# Synth.net
KiCad netlist of a schematic drawn in Altium Designer
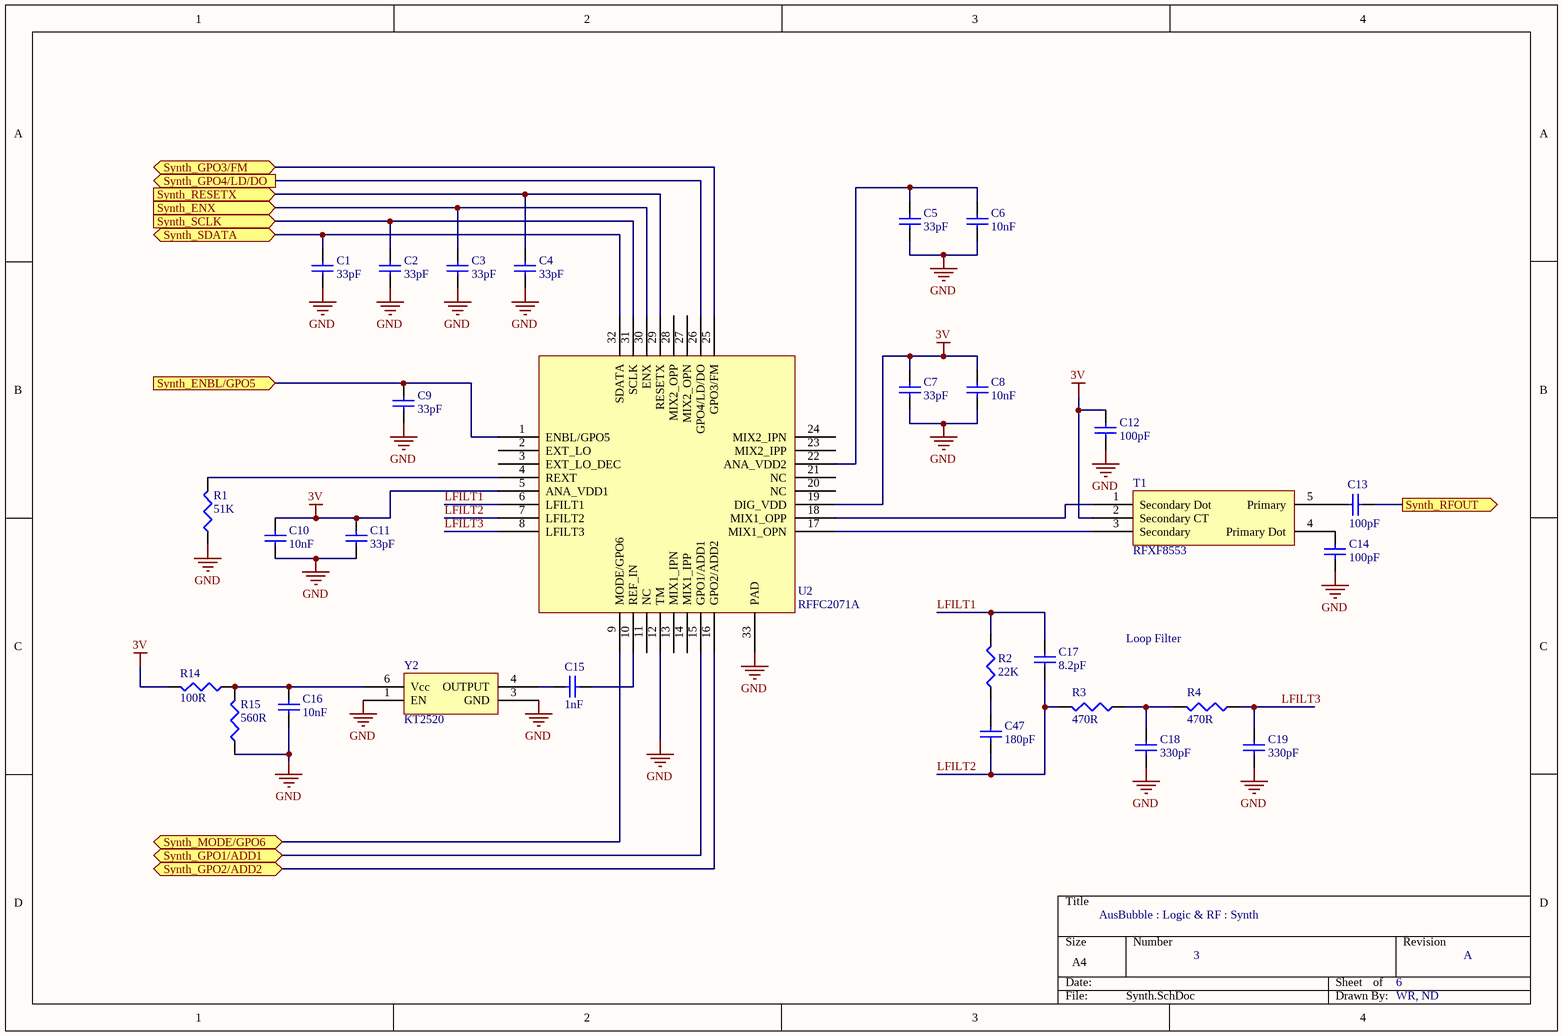
[diagram p0: Synth.SchDoc]

(export (version "E")
  (design (tool "Eeschema 10.0.6"))
  (components
    (comp (ref "C1")
      (value "33pF")
      (footprint "1608[0603]")
      (description "Capacitor (Semiconductor SIM Model)")
      (fields (field (name "Comment") "Cap Semi") (field (name "PUBLISHER") "Altium Limited"))
      (libsource (lib "Miscellaneous Devices") (part "Cap Semi"))
    )
    (comp (ref "C2")
      (value "33pF")
      (footprint "1608[0603]")
      (description "Capacitor (Semiconductor SIM Model)")
      (fields (field (name "Comment") "Cap Semi") (field (name "PUBLISHER") "Altium Limited"))
      (libsource (lib "Miscellaneous Devices") (part "Cap Semi"))
    )
    (comp (ref "C3")
      (value "33pF")
      (footprint "1608[0603]")
      (description "Capacitor (Semiconductor SIM Model)")
      (fields (field (name "Comment") "Cap Semi") (field (name "PUBLISHER") "Altium Limited"))
      (libsource (lib "Miscellaneous Devices") (part "Cap Semi"))
    )
    (comp (ref "C4")
      (value "33pF")
      (footprint "1608[0603]")
      (description "Capacitor (Semiconductor SIM Model)")
      (fields (field (name "Comment") "Cap Semi") (field (name "PUBLISHER") "Altium Limited"))
      (libsource (lib "Miscellaneous Devices") (part "Cap Semi"))
    )
    (comp (ref "C5")
      (value "33pF")
      (footprint "1608[0603]")
      (description "Capacitor (Semiconductor SIM Model)")
      (fields (field (name "Comment") "Cap Semi") (field (name "PUBLISHER") "Altium Limited"))
      (libsource (lib "Miscellaneous Devices") (part "Cap Semi"))
    )
    (comp (ref "C6")
      (value "10nF")
      (footprint "1608[0603]")
      (description "Capacitor (Semiconductor SIM Model)")
      (fields (field (name "Comment") "Cap Semi") (field (name "PUBLISHER") "Altium Limited"))
      (libsource (lib "Miscellaneous Devices") (part "Cap Semi"))
    )
    (comp (ref "C7")
      (value "33pF")
      (footprint "1608[0603]")
      (description "Capacitor (Semiconductor SIM Model)")
      (fields (field (name "Comment") "Cap Semi") (field (name "PUBLISHER") "Altium Limited"))
      (libsource (lib "Miscellaneous Devices") (part "Cap Semi"))
    )
    (comp (ref "C8")
      (value "10nF")
      (footprint "1608[0603]")
      (description "Capacitor (Semiconductor SIM Model)")
      (fields (field (name "Comment") "Cap Semi") (field (name "PUBLISHER") "Altium Limited"))
      (libsource (lib "Miscellaneous Devices") (part "Cap Semi"))
    )
    (comp (ref "C9")
      (value "33pF")
      (footprint "1608[0603]")
      (description "Capacitor (Semiconductor SIM Model)")
      (fields (field (name "Comment") "Cap Semi") (field (name "PUBLISHER") "Altium Limited"))
      (libsource (lib "Miscellaneous Devices") (part "Cap Semi"))
    )
    (comp (ref "C10")
      (value "10nF")
      (footprint "1608[0603]")
      (description "Capacitor (Semiconductor SIM Model)")
      (fields (field (name "Comment") "Cap Semi") (field (name "PUBLISHER") "Altium Limited"))
      (libsource (lib "Miscellaneous Devices") (part "Cap Semi"))
    )
    (comp (ref "C11")
      (value "33pF")
      (footprint "1608[0603]")
      (description "Capacitor (Semiconductor SIM Model)")
      (fields (field (name "Comment") "Cap Semi") (field (name "PUBLISHER") "Altium Limited"))
      (libsource (lib "Miscellaneous Devices") (part "Cap Semi"))
    )
    (comp (ref "C12")
      (value "100pF")
      (footprint "1608[0603]")
      (description "Capacitor (Semiconductor SIM Model)")
      (fields (field (name "Comment") "Cap Semi") (field (name "PUBLISHER") "Altium Limited"))
      (libsource (lib "Miscellaneous Devices") (part "Cap Semi"))
    )
    (comp (ref "C13")
      (value "100pF")
      (footprint "1608[0603]")
      (description "Capacitor (Semiconductor SIM Model)")
      (fields (field (name "Comment") "Cap Semi") (field (name "PUBLISHER") "Altium Limited"))
      (libsource (lib "Miscellaneous Devices") (part "Cap Semi"))
    )
    (comp (ref "C14")
      (value "100pF")
      (footprint "1608[0603]")
      (description "Capacitor (Semiconductor SIM Model)")
      (fields (field (name "Comment") "Cap Semi") (field (name "PUBLISHER") "Altium Limited"))
      (libsource (lib "Miscellaneous Devices") (part "Cap Semi"))
    )
    (comp (ref "C15")
      (value "1nF")
      (footprint "1608[0603]")
      (description "Capacitor (Semiconductor SIM Model)")
      (fields (field (name "Comment") "Cap Semi") (field (name "PUBLISHER") "Altium Limited"))
      (libsource (lib "Miscellaneous Devices") (part "Cap Semi"))
    )
    (comp (ref "C16")
      (value "10nF")
      (footprint "1608[0603]")
      (description "Capacitor (Semiconductor SIM Model)")
      (fields (field (name "Comment") "Cap Semi") (field (name "PUBLISHER") "Altium Limited"))
      (libsource (lib "Miscellaneous Devices") (part "Cap Semi"))
    )
    (comp (ref "C17")
      (value "8.2pF")
      (footprint "1608[0603]")
      (description "Capacitor (Semiconductor SIM Model)")
      (fields (field (name "Comment") "Cap Semi") (field (name "PUBLISHER") "Altium Limited"))
      (libsource (lib "Miscellaneous Devices") (part "Cap Semi"))
    )
    (comp (ref "C18")
      (value "330pF")
      (footprint "1608[0603]")
      (description "Capacitor (Semiconductor SIM Model)")
      (fields (field (name "Comment") "Cap Semi") (field (name "PUBLISHER") "Altium Limited"))
      (libsource (lib "Miscellaneous Devices") (part "Cap Semi"))
    )
    (comp (ref "C19")
      (value "330pF")
      (footprint "1608[0603]")
      (description "Capacitor (Semiconductor SIM Model)")
      (fields (field (name "Comment") "Cap Semi") (field (name "PUBLISHER") "Altium Limited"))
      (libsource (lib "Miscellaneous Devices") (part "Cap Semi"))
    )
    (comp (ref "C47")
      (value "180pF")
      (footprint "1608[0603]")
      (description "Capacitor (Semiconductor SIM Model)")
      (fields (field (name "Comment") "Cap Semi") (field (name "PUBLISHER") "Altium Limited"))
      (libsource (lib "Miscellaneous Devices") (part "Cap Semi"))
    )
    (comp (ref "R1")
      (value "51K")
      (footprint "J1-0603")
      (description "Resistor")
      (fields (field (name "Comment") "Res3") (field (name "PUBLISHER") "Altium Limited"))
      (libsource (lib "Miscellaneous Devices") (part "Res3"))
    )
    (comp (ref "R2")
      (value "22K")
      (footprint "J1-0603")
      (description "Resistor")
      (fields (field (name "Comment") "Res3") (field (name "PUBLISHER") "Altium Limited"))
      (libsource (lib "Miscellaneous Devices") (part "Res3"))
    )
    (comp (ref "R3")
      (value "470R")
      (footprint "J1-0603")
      (description "Resistor")
      (fields (field (name "Comment") "Res3") (field (name "PUBLISHER") "Altium Limited"))
      (libsource (lib "Miscellaneous Devices") (part "Res3"))
    )
    (comp (ref "R4")
      (value "470R")
      (footprint "J1-0603")
      (description "Resistor")
      (fields (field (name "Comment") "Res3") (field (name "PUBLISHER") "Altium Limited"))
      (libsource (lib "Miscellaneous Devices") (part "Res3"))
    )
    (comp (ref "R14")
      (value "100R")
      (footprint "J1-0603")
      (description "Resistor")
      (fields (field (name "Comment") "Res3") (field (name "PUBLISHER") "Altium Limited"))
      (libsource (lib "Miscellaneous Devices") (part "Res3"))
    )
    (comp (ref "R15")
      (value "560R")
      (footprint "J1-0603")
      (description "Resistor")
      (fields (field (name "Comment") "Res3") (field (name "PUBLISHER") "Altium Limited"))
      (libsource (lib "Miscellaneous Devices") (part "Res3"))
    )
    (comp (ref "T1")
      (value "RFXF8553")
      (footprint "RFXF8553")
      (description "1:4 SMT TRANSFORMER")
      (libsource (lib "Logic_RF_Component_Symbols") (part "RFXF8553"))
    )
    (comp (ref "U2")
      (value "RFFC2071A")
      (footprint "QFN50P500X500-32WAL")
      (description "2.7GHz RF SYNTHESIZER/VCO WITH INTEGRATED RF MIXER")
      (libsource (lib "Logic_RF_Component_Symbols") (part "RFFC2071"))
    )
    (comp (ref "Y2")
      (value "KT2520")
      (footprint "KT2520")
      (description "Temperature-Compensated Crystal Oscillator (TCXO) KT2520")
      (libsource (lib "Logic_RF_Component_Symbols") (part "KT2520"))
    )
  )
  (nets
    (net (code "1") (name "/LFILT1") (class "Default")
      (node (ref "C17") (pin "2") (pinfunction "2_2") (pintype "passive"))
      (node (ref "R2") (pin "2") (pinfunction "2_2") (pintype "passive"))
      (node (ref "U2") (pin "6") (pinfunction "LFILT1_6") (pintype "passive"))
    )
    (net (code "2") (name "/LFILT2") (class "Default")
      (node (ref "C17") (pin "1") (pinfunction "1_1") (pintype "passive"))
      (node (ref "C47") (pin "1") (pinfunction "1_1") (pintype "passive"))
      (node (ref "R3") (pin "2") (pinfunction "2_2") (pintype "passive"))
      (node (ref "U2") (pin "7") (pinfunction "LFILT2_7") (pintype "passive"))
    )
    (net (code "3") (name "/LFILT3") (class "Default")
      (node (ref "C19") (pin "2") (pinfunction "2_2") (pintype "passive"))
      (node (ref "R4") (pin "1") (pinfunction "1_1") (pintype "passive"))
      (node (ref "U2") (pin "8") (pinfunction "LFILT3_8") (pintype "passive"))
    )
    (net (code "4") (name "/Synth_ENBL{slash}GPO5") (class "Default")
      (node (ref "C9") (pin "2") (pinfunction "2_2") (pintype "passive"))
      (node (ref "U2") (pin "1") (pinfunction "ENBL/GPO5_1") (pintype "passive"))
    )
    (net (code "5") (name "/Synth_ENX") (class "Default")
      (node (ref "C3") (pin "2") (pinfunction "2_2") (pintype "passive"))
      (node (ref "U2") (pin "30") (pinfunction "ENX_30") (pintype "passive"))
    )
    (net (code "6") (name "/Synth_GPO1{slash}ADD1") (class "Default")
      (node (ref "U2") (pin "15") (pinfunction "GPO1/ADD1_15") (pintype "passive"))
    )
    (net (code "7") (name "/Synth_GPO2{slash}ADD2") (class "Default")
      (node (ref "U2") (pin "16") (pinfunction "GPO2/ADD2_16") (pintype "passive"))
    )
    (net (code "8") (name "/Synth_GPO3{slash}FM") (class "Default")
      (node (ref "U2") (pin "25") (pinfunction "GPO3/FM_25") (pintype "passive"))
    )
    (net (code "9") (name "/Synth_GPO4{slash}LD{slash}DO") (class "Default")
      (node (ref "U2") (pin "26") (pinfunction "GPO4/LD/DO_26") (pintype "passive"))
    )
    (net (code "10") (name "/Synth_MODE{slash}GPO6") (class "Default")
      (node (ref "U2") (pin "9") (pinfunction "MODE/GPO6_9") (pintype "passive"))
    )
    (net (code "11") (name "/Synth_RESETX") (class "Default")
      (node (ref "C4") (pin "2") (pinfunction "2_2") (pintype "passive"))
      (node (ref "U2") (pin "29") (pinfunction "RESETX_29") (pintype "passive"))
    )
    (net (code "12") (name "/Synth_RFOUT") (class "Default")
      (node (ref "C13") (pin "2") (pinfunction "2_2") (pintype "passive"))
    )
    (net (code "13") (name "/Synth_SCLK") (class "Default")
      (node (ref "C2") (pin "2") (pinfunction "2_2") (pintype "passive"))
      (node (ref "U2") (pin "31") (pinfunction "SCLK_31") (pintype "passive"))
    )
    (net (code "14") (name "/Synth_SDATA") (class "Default")
      (node (ref "C1") (pin "2") (pinfunction "2_2") (pintype "passive"))
      (node (ref "U2") (pin "32") (pinfunction "SDATA_32") (pintype "passive"))
    )
    (net (code "15") (name "3V") (class "Default")
      (node (ref "C10") (pin "2") (pinfunction "2_2") (pintype "passive"))
      (node (ref "C11") (pin "2") (pinfunction "2_2") (pintype "passive"))
      (node (ref "C12") (pin "1") (pinfunction "1_1") (pintype "passive"))
      (node (ref "C7") (pin "1") (pinfunction "1_1") (pintype "passive"))
      (node (ref "C8") (pin "1") (pinfunction "1_1") (pintype "passive"))
      (node (ref "R14") (pin "2") (pinfunction "2_2") (pintype "passive"))
      (node (ref "T1") (pin "2") (pinfunction "Secondary_CT_2") (pintype "passive"))
      (node (ref "U2") (pin "19") (pinfunction "DIG_VDD_19") (pintype "passive"))
      (node (ref "U2") (pin "5") (pinfunction "ANA_VDD1_5") (pintype "passive"))
    )
    (net (code "16") (name "GND") (class "Default")
      (node (ref "C1") (pin "1") (pinfunction "1_1") (pintype "passive"))
      (node (ref "C10") (pin "1") (pinfunction "1_1") (pintype "passive"))
      (node (ref "C11") (pin "1") (pinfunction "1_1") (pintype "passive"))
      (node (ref "C12") (pin "2") (pinfunction "2_2") (pintype "passive"))
      (node (ref "C14") (pin "1") (pinfunction "1_1") (pintype "passive"))
      (node (ref "C16") (pin "1") (pinfunction "1_1") (pintype "passive"))
      (node (ref "C18") (pin "1") (pinfunction "1_1") (pintype "passive"))
      (node (ref "C19") (pin "1") (pinfunction "1_1") (pintype "passive"))
      (node (ref "C2") (pin "1") (pinfunction "1_1") (pintype "passive"))
      (node (ref "C3") (pin "1") (pinfunction "1_1") (pintype "passive"))
      (node (ref "C4") (pin "1") (pinfunction "1_1") (pintype "passive"))
      (node (ref "C5") (pin "2") (pinfunction "2_2") (pintype "passive"))
      (node (ref "C6") (pin "2") (pinfunction "2_2") (pintype "passive"))
      (node (ref "C7") (pin "2") (pinfunction "2_2") (pintype "passive"))
      (node (ref "C8") (pin "2") (pinfunction "2_2") (pintype "passive"))
      (node (ref "C9") (pin "1") (pinfunction "1_1") (pintype "passive"))
      (node (ref "R1") (pin "1") (pinfunction "1_1") (pintype "passive"))
      (node (ref "R15") (pin "1") (pinfunction "1_1") (pintype "passive"))
      (node (ref "U2") (pin "12") (pinfunction "TM_12") (pintype "passive"))
      (node (ref "U2") (pin "33") (pinfunction "PAD_33") (pintype "passive"))
      (node (ref "Y2") (pin "1") (pinfunction "EN_1") (pintype "passive"))
      (node (ref "Y2") (pin "3") (pinfunction "GND_3") (pintype "passive"))
    )
    (net (code "17") (name "Net-(C18-Pad2)") (class "Default")
      (node (ref "C18") (pin "2") (pinfunction "2_2") (pintype "passive"))
      (node (ref "R3") (pin "1") (pinfunction "1_1") (pintype "passive"))
      (node (ref "R4") (pin "2") (pinfunction "2_2") (pintype "passive"))
    )
    (net (code "18") (name "Net-(C47-Pad2)") (class "Default")
      (node (ref "C47") (pin "2") (pinfunction "2_2") (pintype "passive"))
      (node (ref "R2") (pin "1") (pinfunction "1_1") (pintype "passive"))
    )
    (net (code "19") (name "Net-(T1-Primary)") (class "Default")
      (node (ref "C13") (pin "1") (pinfunction "1_1") (pintype "passive"))
      (node (ref "T1") (pin "5") (pinfunction "Primary_5") (pintype "passive"))
    )
    (net (code "20") (name "Net-(T1-Primary_Dot)") (class "Default")
      (node (ref "C14") (pin "2") (pinfunction "2_2") (pintype "passive"))
      (node (ref "T1") (pin "4") (pinfunction "Primary_Dot_4") (pintype "passive"))
    )
    (net (code "21") (name "Net-(T1-Secondary)") (class "Default")
      (node (ref "T1") (pin "3") (pinfunction "Secondary_3") (pintype "passive"))
      (node (ref "U2") (pin "17") (pinfunction "MIX1_OPN_17") (pintype "passive"))
    )
    (net (code "22") (name "Net-(T1-Secondary_Dot)") (class "Default")
      (node (ref "T1") (pin "1") (pinfunction "Secondary_Dot_1") (pintype "passive"))
      (node (ref "U2") (pin "18") (pinfunction "MIX1_OPP_18") (pintype "passive"))
    )
    (net (code "23") (name "Net-(U2-ANA_VDD2)") (class "Default")
      (node (ref "C5") (pin "1") (pinfunction "1_1") (pintype "passive"))
      (node (ref "C6") (pin "1") (pinfunction "1_1") (pintype "passive"))
      (node (ref "U2") (pin "22") (pinfunction "ANA_VDD2_22") (pintype "passive"))
    )
    (net (code "24") (name "Net-(U2-REF_IN)") (class "Default")
      (node (ref "C15") (pin "1") (pinfunction "1_1") (pintype "passive"))
      (node (ref "U2") (pin "10") (pinfunction "REF_IN_10") (pintype "passive"))
    )
    (net (code "25") (name "Net-(U2-REXT)") (class "Default")
      (node (ref "R1") (pin "2") (pinfunction "2_2") (pintype "passive"))
      (node (ref "U2") (pin "4") (pinfunction "REXT_4") (pintype "passive"))
    )
    (net (code "26") (name "Net-(Y2-OUTPUT)") (class "Default")
      (node (ref "C15") (pin "2") (pinfunction "2_2") (pintype "passive"))
      (node (ref "Y2") (pin "4") (pinfunction "OUTPUT_4") (pintype "passive"))
    )
    (net (code "27") (name "Net-(Y2-Vcc)") (class "Default")
      (node (ref "C16") (pin "2") (pinfunction "2_2") (pintype "passive"))
      (node (ref "R14") (pin "1") (pinfunction "1_1") (pintype "passive"))
      (node (ref "R15") (pin "2") (pinfunction "2_2") (pintype "passive"))
      (node (ref "Y2") (pin "6") (pinfunction "Vcc_6") (pintype "passive"))
    )
    (net (code "28") (name "unconnected-(U2-EXT_LO-Pad2)") (class "Default")
      (node (ref "U2") (pin "2") (pinfunction "EXT_LO_2") (pintype "passive"))
    )
    (net (code "29") (name "unconnected-(U2-EXT_LO_DEC-Pad3)") (class "Default")
      (node (ref "U2") (pin "3") (pinfunction "EXT_LO_DEC_3") (pintype "passive"))
    )
    (net (code "30") (name "unconnected-(U2-MIX1_IPN-Pad13)") (class "Default")
      (node (ref "U2") (pin "13") (pinfunction "MIX1_IPN_13") (pintype "passive"))
    )
    (net (code "31") (name "unconnected-(U2-MIX1_IPP-Pad14)") (class "Default")
      (node (ref "U2") (pin "14") (pinfunction "MIX1_IPP_14") (pintype "passive"))
    )
    (net (code "32") (name "unconnected-(U2-MIX2_IPN-Pad24)") (class "Default")
      (node (ref "U2") (pin "24") (pinfunction "MIX2_IPN_24") (pintype "passive"))
    )
    (net (code "33") (name "unconnected-(U2-MIX2_IPP-Pad23)") (class "Default")
      (node (ref "U2") (pin "23") (pinfunction "MIX2_IPP_23") (pintype "passive"))
    )
    (net (code "34") (name "unconnected-(U2-MIX2_OPN-Pad27)") (class "Default")
      (node (ref "U2") (pin "27") (pinfunction "MIX2_OPN_27") (pintype "passive"))
    )
    (net (code "35") (name "unconnected-(U2-MIX2_OPP-Pad28)") (class "Default")
      (node (ref "U2") (pin "28") (pinfunction "MIX2_OPP_28") (pintype "passive"))
    )
    (net (code "36") (name "unconnected-(U2-NC-Pad11)") (class "Default")
      (node (ref "U2") (pin "11") (pinfunction "NC_11") (pintype "passive"))
    )
    (net (code "37") (name "unconnected-(U2-NC-Pad20)") (class "Default")
      (node (ref "U2") (pin "20") (pinfunction "NC_20") (pintype "passive"))
    )
    (net (code "38") (name "unconnected-(U2-NC-Pad21)") (class "Default")
      (node (ref "U2") (pin "21") (pinfunction "NC_21") (pintype "passive"))
    )
  )
)
